# XBee.net
KiCad netlist of a schematic drawn in Altium Designer
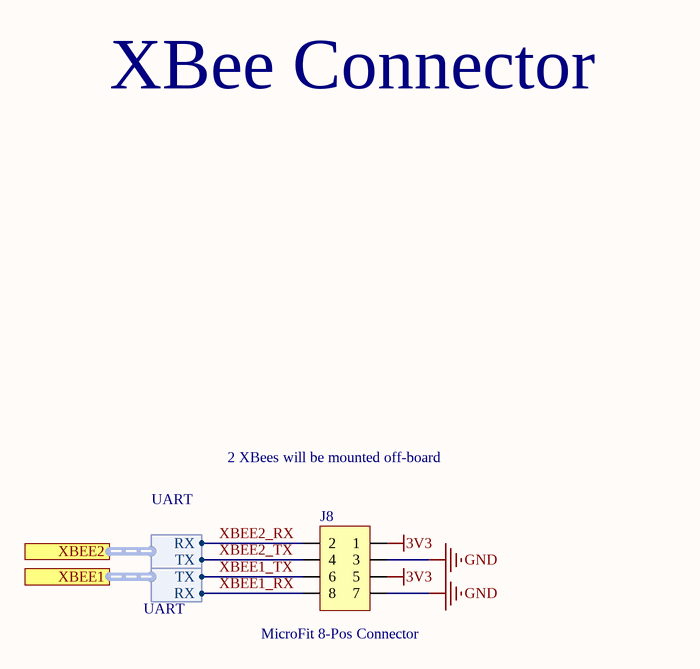
[diagram p0: XBee.SchDoc]

(export (version "E")
  (design (tool "Eeschema 10.0.6"))
  (components
    (comp (ref "J8")
      (value "MicroFit 8-Pos Connector")
      (footprint "Microfit-8Pos")
      (description "Molex MicroFit 8-Pos Connector")
      (libsource (lib "LaunchyRIOComponents") (part "Micro-Fit 8Pos"))
    )
  )
  (nets
    (net (code "2") (name "/XBEE1_RX") (class "Default")
      (node (ref "J8") (pin "8") (pinfunction "8_8") (pintype "passive"))
    )
    (net (code "3") (name "/XBEE1_TX") (class "Default")
      (node (ref "J8") (pin "6") (pinfunction "6_6") (pintype "passive"))
    )
    (net (code "4") (name "/XBEE2_RX") (class "Default")
      (node (ref "J8") (pin "2") (pinfunction "2_2") (pintype "passive"))
    )
    (net (code "5") (name "/XBEE2_TX") (class "Default")
      (node (ref "J8") (pin "4") (pinfunction "4_4") (pintype "passive"))
    )
    (net (code "7") (name "3V3") (class "Default")
      (node (ref "J8") (pin "1") (pinfunction "1_1") (pintype "passive"))
      (node (ref "J8") (pin "5") (pinfunction "5_5") (pintype "passive"))
    )
    (net (code "8") (name "GND") (class "Default")
      (node (ref "J8") (pin "3") (pinfunction "3_3") (pintype "passive"))
      (node (ref "J8") (pin "7") (pinfunction "7_7") (pintype "passive"))
    )
  )
)
